# ppc_ddr2_0.net
KiCad netlist of a schematic drawn in Altium Designer
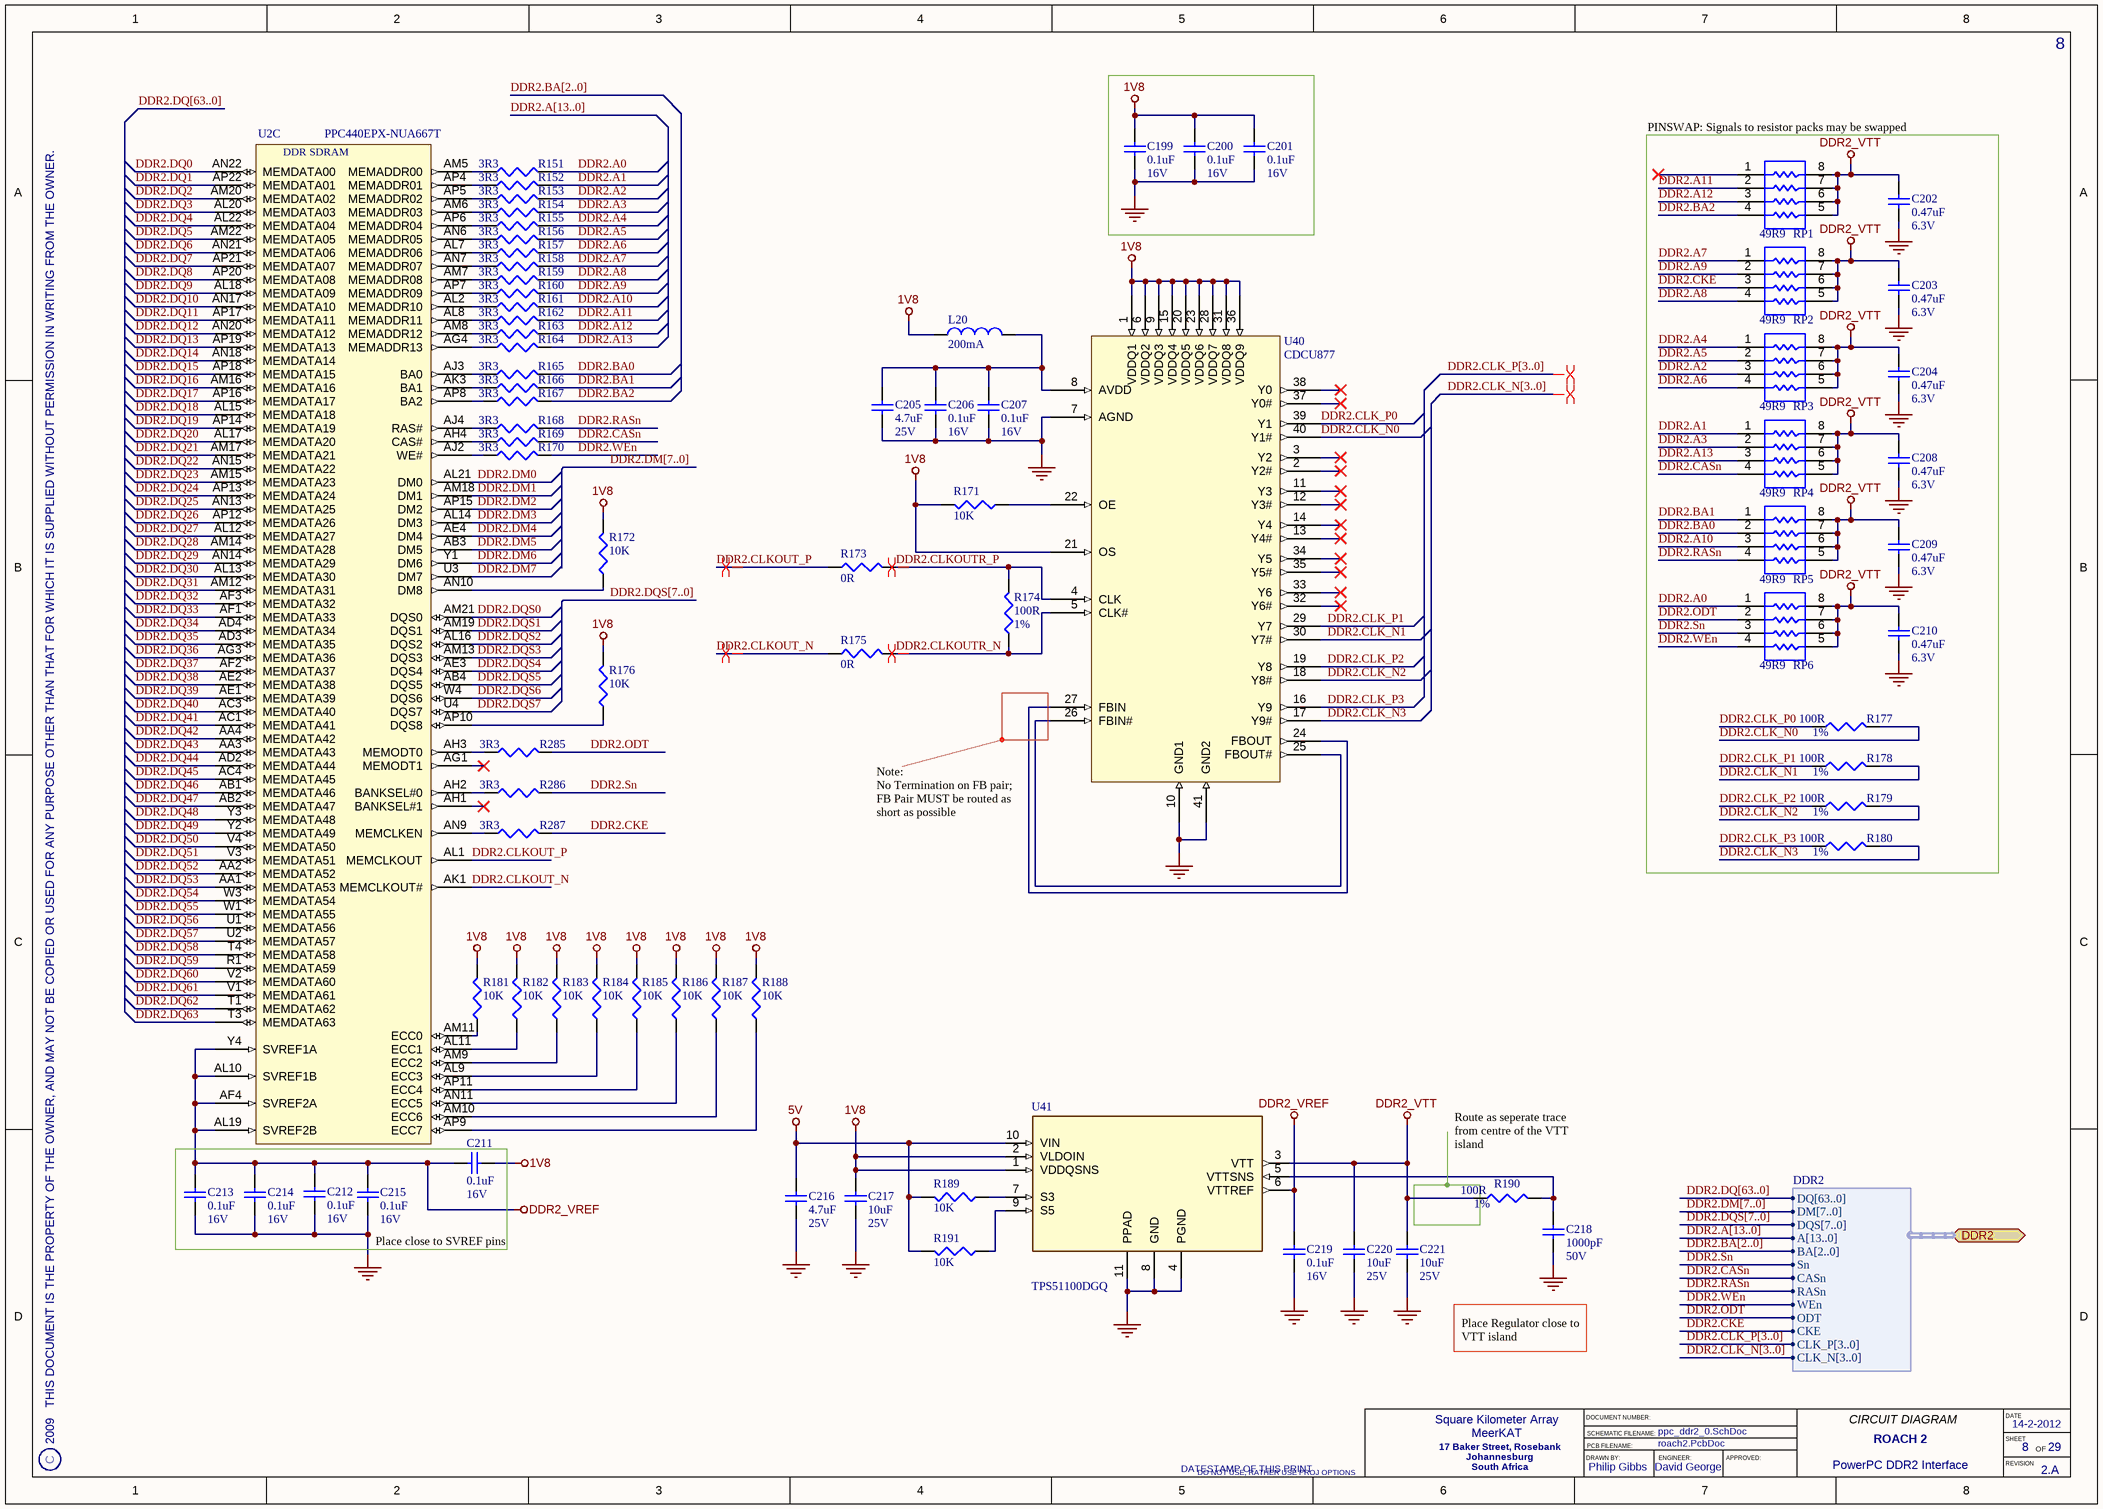
[diagram p0: ppc_ddr2_0.SchDoc]

(export (version "E")
  (design (tool "Eeschema 10.0.6"))
  (components
    (comp (ref "C199")
      (value "0.1uF")
      (footprint "CAPC1005X60L")
      (description "0.1uF, Ceramic Capacitor")
      (fields
        (field (name "RATING") "16V")
        (field (name "MANUFACTURER") "VENKEL")
        (field (name "PARTNUM") "C0402X7R160-104KN")
      )
      (libsource (lib "altium_db") (part "CapStd"))
    )
    (comp (ref "C200")
      (value "0.1uF")
      (footprint "CAPC1005X60L")
      (description "0.1uF, Ceramic Capacitor")
      (fields
        (field (name "RATING") "16V")
        (field (name "MANUFACTURER") "VENKEL")
        (field (name "PARTNUM") "C0402X7R160-104KN")
      )
      (libsource (lib "altium_db") (part "CapStd"))
    )
    (comp (ref "C201")
      (value "0.1uF")
      (footprint "CAPC1005X60L")
      (description "0.1uF, Ceramic Capacitor")
      (fields
        (field (name "RATING") "16V")
        (field (name "MANUFACTURER") "VENKEL")
        (field (name "PARTNUM") "C0402X7R160-104KN")
      )
      (libsource (lib "altium_db") (part "CapStd"))
    )
    (comp (ref "C202")
      (value "0.47uF")
      (footprint "CAPC1005X55L")
      (description "0.47uF, Ceramic Capacitor")
      (fields
        (field (name "RATING") "6.3V")
        (field (name "MANUFACTURER") "MURATA")
        (field (name "PARTNUM") "GRM155R60J474KE19")
      )
      (libsource (lib "altium_db") (part "CapStd"))
    )
    (comp (ref "C203")
      (value "0.47uF")
      (footprint "CAPC1005X55L")
      (description "0.47uF, Ceramic Capacitor")
      (fields
        (field (name "RATING") "6.3V")
        (field (name "MANUFACTURER") "MURATA")
        (field (name "PARTNUM") "GRM155R60J474KE19")
      )
      (libsource (lib "altium_db") (part "CapStd"))
    )
    (comp (ref "C204")
      (value "0.47uF")
      (footprint "CAPC1005X55L")
      (description "0.47uF, Ceramic Capacitor")
      (fields
        (field (name "RATING") "6.3V")
        (field (name "MANUFACTURER") "MURATA")
        (field (name "PARTNUM") "GRM155R60J474KE19")
      )
      (libsource (lib "altium_db") (part "CapStd"))
    )
    (comp (ref "C205")
      (value "4.7uF")
      (footprint "CAPC2012X127L")
      (description "4.7uF, Ceramic Capacitor")
      (fields
        (field (name "RATING") "25V")
        (field (name "MANUFACTURER") "MURATA")
        (field (name "PARTNUM") "GRM21BR61E475KA12K")
      )
      (libsource (lib "altium_db") (part "CapStd"))
    )
    (comp (ref "C206")
      (value "0.1uF")
      (footprint "CAPC1005X60L")
      (description "0.1uF, Ceramic Capacitor")
      (fields
        (field (name "RATING") "16V")
        (field (name "MANUFACTURER") "VENKEL")
        (field (name "PARTNUM") "C0402X7R160-104KN")
      )
      (libsource (lib "altium_db") (part "CapStd"))
    )
    (comp (ref "C207")
      (value "0.1uF")
      (footprint "CAPC1005X60L")
      (description "0.1uF, Ceramic Capacitor")
      (fields
        (field (name "RATING") "16V")
        (field (name "MANUFACTURER") "VENKEL")
        (field (name "PARTNUM") "C0402X7R160-104KN")
      )
      (libsource (lib "altium_db") (part "CapStd"))
    )
    (comp (ref "C208")
      (value "0.47uF")
      (footprint "CAPC1005X55L")
      (description "0.47uF, Ceramic Capacitor")
      (fields
        (field (name "RATING") "6.3V")
        (field (name "MANUFACTURER") "MURATA")
        (field (name "PARTNUM") "GRM155R60J474KE19")
      )
      (libsource (lib "altium_db") (part "CapStd"))
    )
    (comp (ref "C209")
      (value "0.47uF")
      (footprint "CAPC1005X55L")
      (description "0.47uF, Ceramic Capacitor")
      (fields
        (field (name "RATING") "6.3V")
        (field (name "MANUFACTURER") "MURATA")
        (field (name "PARTNUM") "GRM155R60J474KE19")
      )
      (libsource (lib "altium_db") (part "CapStd"))
    )
    (comp (ref "C210")
      (value "0.47uF")
      (footprint "CAPC1005X55L")
      (description "0.47uF, Ceramic Capacitor")
      (fields
        (field (name "RATING") "6.3V")
        (field (name "MANUFACTURER") "MURATA")
        (field (name "PARTNUM") "GRM155R60J474KE19")
      )
      (libsource (lib "altium_db") (part "CapStd"))
    )
    (comp (ref "C211")
      (value "0.1uF")
      (footprint "CAPC1005X60L")
      (description "0.1uF, Ceramic Capacitor")
      (fields
        (field (name "RATING") "16V")
        (field (name "MANUFACTURER") "VENKEL")
        (field (name "PARTNUM") "C0402X7R160-104KN")
      )
      (libsource (lib "altium_db") (part "CapStd"))
    )
    (comp (ref "C212")
      (value "0.1uF")
      (footprint "CAPC1005X60L")
      (description "0.1uF, Ceramic Capacitor")
      (fields
        (field (name "RATING") "16V")
        (field (name "MANUFACTURER") "VENKEL")
        (field (name "PARTNUM") "C0402X7R160-104KN")
      )
      (libsource (lib "altium_db") (part "CapStd"))
    )
    (comp (ref "C213")
      (value "0.1uF")
      (footprint "CAPC1005X60L")
      (description "0.1uF, Ceramic Capacitor")
      (fields
        (field (name "RATING") "16V")
        (field (name "MANUFACTURER") "VENKEL")
        (field (name "PARTNUM") "C0402X7R160-104KN")
      )
      (libsource (lib "altium_db") (part "CapStd"))
    )
    (comp (ref "C214")
      (value "0.1uF")
      (footprint "CAPC1005X60L")
      (description "0.1uF, Ceramic Capacitor")
      (fields
        (field (name "RATING") "16V")
        (field (name "MANUFACTURER") "VENKEL")
        (field (name "PARTNUM") "C0402X7R160-104KN")
      )
      (libsource (lib "altium_db") (part "CapStd"))
    )
    (comp (ref "C215")
      (value "0.1uF")
      (footprint "CAPC1005X60L")
      (description "0.1uF, Ceramic Capacitor")
      (fields
        (field (name "RATING") "16V")
        (field (name "MANUFACTURER") "VENKEL")
        (field (name "PARTNUM") "C0402X7R160-104KN")
      )
      (libsource (lib "altium_db") (part "CapStd"))
    )
    (comp (ref "C216")
      (value "4.7uF")
      (footprint "CAPC2012X127L")
      (description "4.7uF, Ceramic Capacitor")
      (fields
        (field (name "RATING") "25V")
        (field (name "MANUFACTURER") "MURATA")
        (field (name "PARTNUM") "GRM21BR61E475KA12K")
      )
      (libsource (lib "altium_db") (part "CapStd"))
    )
    (comp (ref "C217")
      (value "10uF")
      (footprint "CAPC3225X200L")
      (description "10uF, Ceramic Capacitor")
      (fields
        (field (name "RATING") "25V")
        (field (name "MANUFACTURER") "MURATA")
        (field (name "PARTNUM") "GRM32DR61E106KA12L")
      )
      (libsource (lib "altium_db") (part "CapStd"))
    )
    (comp (ref "C218")
      (value "1000pF")
      (footprint "CAPC1005X55L")
      (description "1000pF, Ceramic Capacitor")
      (fields
        (field (name "RATING") "50V")
        (field (name "MANUFACTURER") "MURATA")
        (field (name "PARTNUM") "GRM155R61H102KA01D")
      )
      (libsource (lib "altium_db") (part "CapStd"))
    )
    (comp (ref "C219")
      (value "0.1uF")
      (footprint "CAPC1005X60L")
      (description "0.1uF, Ceramic Capacitor")
      (fields
        (field (name "RATING") "16V")
        (field (name "MANUFACTURER") "VENKEL")
        (field (name "PARTNUM") "C0402X7R160-104KN")
      )
      (libsource (lib "altium_db") (part "CapStd"))
    )
    (comp (ref "C220")
      (value "10uF")
      (footprint "CAPC3225X200L")
      (description "10uF, Ceramic Capacitor")
      (fields
        (field (name "RATING") "25V")
        (field (name "MANUFACTURER") "MURATA")
        (field (name "PARTNUM") "GRM32DR61E106KA12L")
      )
      (libsource (lib "altium_db") (part "CapStd"))
    )
    (comp (ref "C221")
      (value "10uF")
      (footprint "CAPC3225X200L")
      (description "10uF, Ceramic Capacitor")
      (fields
        (field (name "RATING") "25V")
        (field (name "MANUFACTURER") "MURATA")
        (field (name "PARTNUM") "GRM32DR61E106KA12L")
      )
      (libsource (lib "altium_db") (part "CapStd"))
    )
    (comp (ref "L20")
      (value "600R")
      (footprint "INDC2012X130L")
      (description "600 Ohm, Chip Ferrite Bead")
      (fields
        (field (name "RATING") "200mA")
        (field (name "MANUFACTURER") "Murata")
        (field (name "PARTNUM") "BLM21BD601SN1")
      )
      (libsource (lib "altium_db") (part "IndStd"))
    )
    (comp (ref "R151")
      (value "3R3")
      (footprint "RESC1005X40L")
      (description "3R3, 1.1mm x 0.5mm, Thick Film Resistor")
      (fields (field (name "MANUFACTURER") "ROYALOHM") (field (name "PARTNUM") "0402WGJ330KT1E"))
      (libsource (lib "altium_db") (part "ResStd"))
    )
    (comp (ref "R152")
      (value "3R3")
      (footprint "RESC1005X40L")
      (description "3R3, 1.1mm x 0.5mm, Thick Film Resistor")
      (fields (field (name "MANUFACTURER") "ROYALOHM") (field (name "PARTNUM") "0402WGJ330KT1E"))
      (libsource (lib "altium_db") (part "ResStd"))
    )
    (comp (ref "R153")
      (value "3R3")
      (footprint "RESC1005X40L")
      (description "3R3, 1.1mm x 0.5mm, Thick Film Resistor")
      (fields (field (name "MANUFACTURER") "ROYALOHM") (field (name "PARTNUM") "0402WGJ330KT1E"))
      (libsource (lib "altium_db") (part "ResStd"))
    )
    (comp (ref "R154")
      (value "3R3")
      (footprint "RESC1005X40L")
      (description "3R3, 1.1mm x 0.5mm, Thick Film Resistor")
      (fields (field (name "MANUFACTURER") "ROYALOHM") (field (name "PARTNUM") "0402WGJ330KT1E"))
      (libsource (lib "altium_db") (part "ResStd"))
    )
    (comp (ref "R155")
      (value "3R3")
      (footprint "RESC1005X40L")
      (description "3R3, 1.1mm x 0.5mm, Thick Film Resistor")
      (fields (field (name "MANUFACTURER") "ROYALOHM") (field (name "PARTNUM") "0402WGJ330KT1E"))
      (libsource (lib "altium_db") (part "ResStd"))
    )
    (comp (ref "R156")
      (value "3R3")
      (footprint "RESC1005X40L")
      (description "3R3, 1.1mm x 0.5mm, Thick Film Resistor")
      (fields (field (name "MANUFACTURER") "ROYALOHM") (field (name "PARTNUM") "0402WGJ330KT1E"))
      (libsource (lib "altium_db") (part "ResStd"))
    )
    (comp (ref "R157")
      (value "3R3")
      (footprint "RESC1005X40L")
      (description "3R3, 1.1mm x 0.5mm, Thick Film Resistor")
      (fields (field (name "MANUFACTURER") "ROYALOHM") (field (name "PARTNUM") "0402WGJ330KT1E"))
      (libsource (lib "altium_db") (part "ResStd"))
    )
    (comp (ref "R158")
      (value "3R3")
      (footprint "RESC1005X40L")
      (description "3R3, 1.1mm x 0.5mm, Thick Film Resistor")
      (fields (field (name "MANUFACTURER") "ROYALOHM") (field (name "PARTNUM") "0402WGJ330KT1E"))
      (libsource (lib "altium_db") (part "ResStd"))
    )
    (comp (ref "R159")
      (value "3R3")
      (footprint "RESC1005X40L")
      (description "3R3, 1.1mm x 0.5mm, Thick Film Resistor")
      (fields (field (name "MANUFACTURER") "ROYALOHM") (field (name "PARTNUM") "0402WGJ330KT1E"))
      (libsource (lib "altium_db") (part "ResStd"))
    )
    (comp (ref "R160")
      (value "3R3")
      (footprint "RESC1005X40L")
      (description "3R3, 1.1mm x 0.5mm, Thick Film Resistor")
      (fields (field (name "MANUFACTURER") "ROYALOHM") (field (name "PARTNUM") "0402WGJ330KT1E"))
      (libsource (lib "altium_db") (part "ResStd"))
    )
    (comp (ref "R161")
      (value "3R3")
      (footprint "RESC1005X40L")
      (description "3R3, 1.1mm x 0.5mm, Thick Film Resistor")
      (fields (field (name "MANUFACTURER") "ROYALOHM") (field (name "PARTNUM") "0402WGJ330KT1E"))
      (libsource (lib "altium_db") (part "ResStd"))
    )
    (comp (ref "R162")
      (value "3R3")
      (footprint "RESC1005X40L")
      (description "3R3, 1.1mm x 0.5mm, Thick Film Resistor")
      (fields (field (name "MANUFACTURER") "ROYALOHM") (field (name "PARTNUM") "0402WGJ330KT1E"))
      (libsource (lib "altium_db") (part "ResStd"))
    )
    (comp (ref "R163")
      (value "3R3")
      (footprint "RESC1005X40L")
      (description "3R3, 1.1mm x 0.5mm, Thick Film Resistor")
      (fields (field (name "MANUFACTURER") "ROYALOHM") (field (name "PARTNUM") "0402WGJ330KT1E"))
      (libsource (lib "altium_db") (part "ResStd"))
    )
    (comp (ref "R164")
      (value "3R3")
      (footprint "RESC1005X40L")
      (description "3R3, 1.1mm x 0.5mm, Thick Film Resistor")
      (fields (field (name "MANUFACTURER") "ROYALOHM") (field (name "PARTNUM") "0402WGJ330KT1E"))
      (libsource (lib "altium_db") (part "ResStd"))
    )
    (comp (ref "R165")
      (value "3R3")
      (footprint "RESC1005X40L")
      (description "3R3, 1.1mm x 0.5mm, Thick Film Resistor")
      (fields (field (name "MANUFACTURER") "ROYALOHM") (field (name "PARTNUM") "0402WGJ330KT1E"))
      (libsource (lib "altium_db") (part "ResStd"))
    )
    (comp (ref "R166")
      (value "3R3")
      (footprint "RESC1005X40L")
      (description "3R3, 1.1mm x 0.5mm, Thick Film Resistor")
      (fields (field (name "MANUFACTURER") "ROYALOHM") (field (name "PARTNUM") "0402WGJ330KT1E"))
      (libsource (lib "altium_db") (part "ResStd"))
    )
    (comp (ref "R167")
      (value "3R3")
      (footprint "RESC1005X40L")
      (description "3R3, 1.1mm x 0.5mm, Thick Film Resistor")
      (fields (field (name "MANUFACTURER") "ROYALOHM") (field (name "PARTNUM") "0402WGJ330KT1E"))
      (libsource (lib "altium_db") (part "ResStd"))
    )
    (comp (ref "R168")
      (value "3R3")
      (footprint "RESC1005X40L")
      (description "3R3, 1.1mm x 0.5mm, Thick Film Resistor")
      (fields (field (name "MANUFACTURER") "ROYALOHM") (field (name "PARTNUM") "0402WGJ330KT1E"))
      (libsource (lib "altium_db") (part "ResStd"))
    )
    (comp (ref "R169")
      (value "3R3")
      (footprint "RESC1005X40L")
      (description "3R3, 1.1mm x 0.5mm, Thick Film Resistor")
      (fields (field (name "MANUFACTURER") "ROYALOHM") (field (name "PARTNUM") "0402WGJ330KT1E"))
      (libsource (lib "altium_db") (part "ResStd"))
    )
    (comp (ref "R170")
      (value "3R3")
      (footprint "RESC1005X40L")
      (description "3R3, 1.1mm x 0.5mm, Thick Film Resistor")
      (fields (field (name "MANUFACTURER") "ROYALOHM") (field (name "PARTNUM") "0402WGJ330KT1E"))
      (libsource (lib "altium_db") (part "ResStd"))
    )
    (comp (ref "R171")
      (value "10K")
      (footprint "RESC1005X40L")
      (description "10K, 1.1mm x 0.5mm, Thick Film Resistor")
      (fields (field (name "MANUFACTURER") "ROYALOHM") (field (name "PARTNUM") "0402WGJ0103T1E"))
      (libsource (lib "altium_db") (part "ResStd"))
    )
    (comp (ref "R172")
      (value "10K")
      (footprint "RESC1005X40L")
      (description "10K, 1.1mm x 0.5mm, Thick Film Resistor")
      (fields (field (name "MANUFACTURER") "ROYALOHM") (field (name "PARTNUM") "0402WGJ0103T1E"))
      (libsource (lib "altium_db") (part "ResStd"))
    )
    (comp (ref "R173")
      (value "0R")
      (footprint "RESC1005X40L")
      (description "0R, 1.1mm x 0.5mm, Thick Film Resistor")
      (fields (field (name "MANUFACTURER") "ROYALOHM") (field (name "PARTNUM") "0402WG00000T1E"))
      (libsource (lib "altium_db") (part "ResStd"))
    )
    (comp (ref "R174")
      (value "100R")
      (footprint "RESC1005X40L")
      (description "100R, 1.1mm x 0.5mm, Thick Film Resistor")
      (fields
        (field (name "MANUFACTURER") "ROYALOHM")
        (field (name "PARTNUM") "0402WGF0101T1E")
        (field (name "TOLERANCE") "1%")
      )
      (libsource (lib "altium_db") (part "ResStd"))
    )
    (comp (ref "R175")
      (value "0R")
      (footprint "RESC1005X40L")
      (description "0R, 1.1mm x 0.5mm, Thick Film Resistor")
      (fields (field (name "MANUFACTURER") "ROYALOHM") (field (name "PARTNUM") "0402WG00000T1E"))
      (libsource (lib "altium_db") (part "ResStd"))
    )
    (comp (ref "R176")
      (value "10K")
      (footprint "RESC1005X40L")
      (description "10K, 1.1mm x 0.5mm, Thick Film Resistor")
      (fields (field (name "MANUFACTURER") "ROYALOHM") (field (name "PARTNUM") "0402WGJ0103T1E"))
      (libsource (lib "altium_db") (part "ResStd"))
    )
    (comp (ref "R177")
      (value "100R")
      (footprint "RESC1005X40L")
      (description "100R, 1.1mm x 0.5mm, Thick Film Resistor")
      (fields
        (field (name "MANUFACTURER") "ROYALOHM")
        (field (name "PARTNUM") "0402WGF0101T1E")
        (field (name "TOLERANCE") "1%")
      )
      (libsource (lib "altium_db") (part "ResStd"))
    )
    (comp (ref "R178")
      (value "100R")
      (footprint "RESC1005X40L")
      (description "100R, 1.1mm x 0.5mm, Thick Film Resistor")
      (fields
        (field (name "MANUFACTURER") "ROYALOHM")
        (field (name "PARTNUM") "0402WGF0101T1E")
        (field (name "TOLERANCE") "1%")
      )
      (libsource (lib "altium_db") (part "ResStd"))
    )
    (comp (ref "R179")
      (value "100R")
      (footprint "RESC1005X40L")
      (description "100R, 1.1mm x 0.5mm, Thick Film Resistor")
      (fields
        (field (name "MANUFACTURER") "ROYALOHM")
        (field (name "PARTNUM") "0402WGF0101T1E")
        (field (name "TOLERANCE") "1%")
      )
      (libsource (lib "altium_db") (part "ResStd"))
    )
    (comp (ref "R180")
      (value "100R")
      (footprint "RESC1005X40L")
      (description "100R, 1.1mm x 0.5mm, Thick Film Resistor")
      (fields
        (field (name "MANUFACTURER") "ROYALOHM")
        (field (name "PARTNUM") "0402WGF0101T1E")
        (field (name "TOLERANCE") "1%")
      )
      (libsource (lib "altium_db") (part "ResStd"))
    )
    (comp (ref "R181")
      (value "10K")
      (footprint "RESC1005X40L")
      (description "10K, 1.1mm x 0.5mm, Thick Film Resistor")
      (fields (field (name "MANUFACTURER") "ROYALOHM") (field (name "PARTNUM") "0402WGJ0103T1E"))
      (libsource (lib "altium_db") (part "ResStd"))
    )
    (comp (ref "R182")
      (value "10K")
      (footprint "RESC1005X40L")
      (description "10K, 1.1mm x 0.5mm, Thick Film Resistor")
      (fields (field (name "MANUFACTURER") "ROYALOHM") (field (name "PARTNUM") "0402WGJ0103T1E"))
      (libsource (lib "altium_db") (part "ResStd"))
    )
    (comp (ref "R183")
      (value "10K")
      (footprint "RESC1005X40L")
      (description "10K, 1.1mm x 0.5mm, Thick Film Resistor")
      (fields (field (name "MANUFACTURER") "ROYALOHM") (field (name "PARTNUM") "0402WGJ0103T1E"))
      (libsource (lib "altium_db") (part "ResStd"))
    )
    (comp (ref "R184")
      (value "10K")
      (footprint "RESC1005X40L")
      (description "10K, 1.1mm x 0.5mm, Thick Film Resistor")
      (fields (field (name "MANUFACTURER") "ROYALOHM") (field (name "PARTNUM") "0402WGJ0103T1E"))
      (libsource (lib "altium_db") (part "ResStd"))
    )
    (comp (ref "R185")
      (value "10K")
      (footprint "RESC1005X40L")
      (description "10K, 1.1mm x 0.5mm, Thick Film Resistor")
      (fields (field (name "MANUFACTURER") "ROYALOHM") (field (name "PARTNUM") "0402WGJ0103T1E"))
      (libsource (lib "altium_db") (part "ResStd"))
    )
    (comp (ref "R186")
      (value "10K")
      (footprint "RESC1005X40L")
      (description "10K, 1.1mm x 0.5mm, Thick Film Resistor")
      (fields (field (name "MANUFACTURER") "ROYALOHM") (field (name "PARTNUM") "0402WGJ0103T1E"))
      (libsource (lib "altium_db") (part "ResStd"))
    )
    (comp (ref "R187")
      (value "10K")
      (footprint "RESC1005X40L")
      (description "10K, 1.1mm x 0.5mm, Thick Film Resistor")
      (fields (field (name "MANUFACTURER") "ROYALOHM") (field (name "PARTNUM") "0402WGJ0103T1E"))
      (libsource (lib "altium_db") (part "ResStd"))
    )
    (comp (ref "R188")
      (value "10K")
      (footprint "RESC1005X40L")
      (description "10K, 1.1mm x 0.5mm, Thick Film Resistor")
      (fields (field (name "MANUFACTURER") "ROYALOHM") (field (name "PARTNUM") "0402WGJ0103T1E"))
      (libsource (lib "altium_db") (part "ResStd"))
    )
    (comp (ref "R189")
      (value "10K")
      (footprint "RESC1005X40L")
      (description "10K, 1.1mm x 0.5mm, Thick Film Resistor")
      (fields (field (name "MANUFACTURER") "ROYALOHM") (field (name "PARTNUM") "0402WGJ0103T1E"))
      (libsource (lib "altium_db") (part "ResStd"))
    )
    (comp (ref "R190")
      (value "100R")
      (footprint "RESC1005X40L")
      (description "100R, 1.1mm x 0.5mm, Thick Film Resistor")
      (fields
        (field (name "MANUFACTURER") "ROYALOHM")
        (field (name "PARTNUM") "0402WGF0101T1E")
        (field (name "TOLERANCE") "1%")
      )
      (libsource (lib "altium_db") (part "ResStd"))
    )
    (comp (ref "R191")
      (value "10K")
      (footprint "RESC1005X40L")
      (description "10K, 1.1mm x 0.5mm, Thick Film Resistor")
      (fields (field (name "MANUFACTURER") "ROYALOHM") (field (name "PARTNUM") "0402WGJ0103T1E"))
      (libsource (lib "altium_db") (part "ResStd"))
    )
    (comp (ref "R285")
      (value "3R3")
      (footprint "RESC1005X40L")
      (description "3R3, 1.1mm x 0.5mm, Thick Film Resistor")
      (fields (field (name "MANUFACTURER") "ROYALOHM") (field (name "PARTNUM") "0402WGJ330KT1E"))
      (libsource (lib "altium_db") (part "ResStd"))
    )
    (comp (ref "R286")
      (value "3R3")
      (footprint "RESC1005X40L")
      (description "3R3, 1.1mm x 0.5mm, Thick Film Resistor")
      (fields (field (name "MANUFACTURER") "ROYALOHM") (field (name "PARTNUM") "0402WGJ330KT1E"))
      (libsource (lib "altium_db") (part "ResStd"))
    )
    (comp (ref "R287")
      (value "3R3")
      (footprint "RESC1005X40L")
      (description "3R3, 1.1mm x 0.5mm, Thick Film Resistor")
      (fields (field (name "MANUFACTURER") "ROYALOHM") (field (name "PARTNUM") "0402WGJ330KT1E"))
      (libsource (lib "altium_db") (part "ResStd"))
    )
    (comp (ref "RP1")
      (value "49R9")
      (footprint "RESCAV50P100X200X45-8L")
      (description "4-Wide, Isolated, Thick Film Resistor Network")
      (fields (field (name "MANUFACTURER") "ROYALOHM") (field (name "PARTNUM") "4D02WGJ0510B1E"))
      (libsource (lib "altium_db") (part "ResPack4"))
    )
    (comp (ref "RP2")
      (value "49R9")
      (footprint "RESCAV50P100X200X45-8L")
      (description "4-Wide, Isolated, Thick Film Resistor Network")
      (fields (field (name "MANUFACTURER") "ROYALOHM") (field (name "PARTNUM") "4D02WGJ0510B1E"))
      (libsource (lib "altium_db") (part "ResPack4"))
    )
    (comp (ref "RP3")
      (value "49R9")
      (footprint "RESCAV50P100X200X45-8L")
      (description "4-Wide, Isolated, Thick Film Resistor Network")
      (fields (field (name "MANUFACTURER") "ROYALOHM") (field (name "PARTNUM") "4D02WGJ0510B1E"))
      (libsource (lib "altium_db") (part "ResPack4"))
    )
    (comp (ref "RP4")
      (value "49R9")
      (footprint "RESCAV50P100X200X45-8L")
      (description "4-Wide, Isolated, Thick Film Resistor Network")
      (fields (field (name "MANUFACTURER") "ROYALOHM") (field (name "PARTNUM") "4D02WGJ0510B1E"))
      (libsource (lib "altium_db") (part "ResPack4"))
    )
    (comp (ref "RP5")
      (value "49R9")
      (footprint "RESCAV50P100X200X45-8L")
      (description "4-Wide, Isolated, Thick Film Resistor Network")
      (fields (field (name "MANUFACTURER") "ROYALOHM") (field (name "PARTNUM") "4D02WGJ0510B1E"))
      (libsource (lib "altium_db") (part "ResPack4"))
    )
    (comp (ref "RP6")
      (value "49R9")
      (footprint "RESCAV50P100X200X45-8L")
      (description "4-Wide, Isolated, Thick Film Resistor Network")
      (fields (field (name "MANUFACTURER") "ROYALOHM") (field (name "PARTNUM") "4D02WGJ0510B1E"))
      (libsource (lib "altium_db") (part "ResPack4"))
    )
    (comp (ref "U2")
      (value "PPC440EPX-NUA667T")
      (footprint "TE-PBGA680")
      (description "667MHz, non-RoHS, PPC440EPx uProcessor")
      (fields (field (name "MANUFACTURER") "Applied Micro"))
      (libsource (lib "altium_db") (part "PPC440EPX"))
    )
    (comp (ref "U40")
      (value "CDCU877")
      (footprint "TQFN-40")
      (description "SSTL Zero-Delay Clock Buffer")
      (fields (field (name "MANUFACTURER") "Texas Instruments"))
      (libsource (lib "altium_db") (part "CDCU877"))
    )
    (comp (ref "U41")
      (value "TPS51100DGQ")
      (footprint "MSOP_10-N")
      (description "3A Sink/Source Regulator")
      (fields (field (name "MANUFACTURER") "Texas Instruments"))
      (libsource (lib "altium_db") (part "TPS51100DGQ"))
    )
  )
  (nets
    (net (code "2") (name "/DDR2.A0") (class "Default")
      (node (ref "R151") (pin "2") (pinfunction "2_2") (pintype "passive"))
      (node (ref "RP6") (pin "1") (pinfunction "1_1") (pintype "passive"))
    )
    (net (code "3") (name "/DDR2.A1") (class "Default")
      (node (ref "R152") (pin "2") (pinfunction "2_2") (pintype "passive"))
      (node (ref "RP4") (pin "1") (pinfunction "1_1") (pintype "passive"))
    )
    (net (code "4") (name "/DDR2.A2") (class "Default")
      (node (ref "R153") (pin "2") (pinfunction "2_2") (pintype "passive"))
      (node (ref "RP3") (pin "3") (pinfunction "3_3") (pintype "passive"))
    )
    (net (code "5") (name "/DDR2.A3") (class "Default")
      (node (ref "R154") (pin "2") (pinfunction "2_2") (pintype "passive"))
      (node (ref "RP4") (pin "2") (pinfunction "2_2") (pintype "passive"))
    )
    (net (code "6") (name "/DDR2.A4") (class "Default")
      (node (ref "R155") (pin "2") (pinfunction "2_2") (pintype "passive"))
      (node (ref "RP3") (pin "1") (pinfunction "1_1") (pintype "passive"))
    )
    (net (code "7") (name "/DDR2.A5") (class "Default")
      (node (ref "R156") (pin "2") (pinfunction "2_2") (pintype "passive"))
      (node (ref "RP3") (pin "2") (pinfunction "2_2") (pintype "passive"))
    )
    (net (code "8") (name "/DDR2.A6") (class "Default")
      (node (ref "R157") (pin "2") (pinfunction "2_2") (pintype "passive"))
      (node (ref "RP3") (pin "4") (pinfunction "4_4") (pintype "passive"))
    )
    (net (code "9") (name "/DDR2.A7") (class "Default")
      (node (ref "R158") (pin "2") (pinfunction "2_2") (pintype "passive"))
      (node (ref "RP2") (pin "1") (pinfunction "1_1") (pintype "passive"))
    )
    (net (code "10") (name "/DDR2.A8") (class "Default")
      (node (ref "R159") (pin "2") (pinfunction "2_2") (pintype "passive"))
      (node (ref "RP2") (pin "4") (pinfunction "4_4") (pintype "passive"))
    )
    (net (code "11") (name "/DDR2.A9") (class "Default")
      (node (ref "R160") (pin "2") (pinfunction "2_2") (pintype "passive"))
      (node (ref "RP2") (pin "2") (pinfunction "2_2") (pintype "passive"))
    )
    (net (code "12") (name "/DDR2.A10") (class "Default")
      (node (ref "R161") (pin "2") (pinfunction "2_2") (pintype "passive"))
      (node (ref "RP5") (pin "3") (pinfunction "3_3") (pintype "passive"))
    )
    (net (code "13") (name "/DDR2.A11") (class "Default")
      (node (ref "R162") (pin "2") (pinfunction "2_2") (pintype "passive"))
      (node (ref "RP1") (pin "2") (pinfunction "2_2") (pintype "passive"))
    )
    (net (code "14") (name "/DDR2.A12") (class "Default")
      (node (ref "R163") (pin "2") (pinfunction "2_2") (pintype "passive"))
      (node (ref "RP1") (pin "3") (pinfunction "3_3") (pintype "passive"))
    )
    (net (code "15") (name "/DDR2.A13") (class "Default")
      (node (ref "R164") (pin "2") (pinfunction "2_2") (pintype "passive"))
      (node (ref "RP4") (pin "3") (pinfunction "3_3") (pintype "passive"))
    )
    (net (code "17") (name "/DDR2.BA0") (class "Default")
      (node (ref "R165") (pin "2") (pinfunction "2_2") (pintype "passive"))
      (node (ref "RP5") (pin "2") (pinfunction "2_2") (pintype "passive"))
    )
    (net (code "18") (name "/DDR2.BA1") (class "Default")
      (node (ref "R166") (pin "2") (pinfunction "2_2") (pintype "passive"))
      (node (ref "RP5") (pin "1") (pinfunction "1_1") (pintype "passive"))
    )
    (net (code "19") (name "/DDR2.BA2") (class "Default")
      (node (ref "R167") (pin "2") (pinfunction "2_2") (pintype "passive"))
      (node (ref "RP1") (pin "4") (pinfunction "4_4") (pintype "passive"))
    )
    (net (code "21") (name "/DDR2.CASn") (class "Default")
      (node (ref "R169") (pin "2") (pinfunction "2_2") (pintype "passive"))
      (node (ref "RP4") (pin "4") (pinfunction "4_4") (pintype "passive"))
    )
    (net (code "22") (name "/DDR2.CKE") (class "Default")
      (node (ref "R287") (pin "2") (pinfunction "2_2") (pintype "passive"))
      (node (ref "RP2") (pin "3") (pinfunction "3_3") (pintype "passive"))
    )
    (net (code "23") (name "/DDR2.CLKOUTR_N") (class "Default")
      (node (ref "R174") (pin "1") (pinfunction "1_1") (pintype "passive"))
      (node (ref "R175") (pin "2") (pinfunction "2_2") (pintype "passive"))
      (node (ref "U40") (pin "5") (pinfunction "CLK#_5") (pintype "input"))
    )
    (net (code "24") (name "/DDR2.CLKOUTR_P") (class "Default")
      (node (ref "R173") (pin "2") (pinfunction "2_2") (pintype "passive"))
      (node (ref "R174") (pin "2") (pinfunction "2_2") (pintype "passive"))
      (node (ref "U40") (pin "4") (pinfunction "CLK_4") (pintype "input"))
    )
    (net (code "25") (name "/DDR2.CLKOUT_N") (class "Default")
      (node (ref "R175") (pin "1") (pinfunction "1_1") (pintype "passive"))
      (node (ref "U2") (pin "AK1") (pinfunction "MEMCLKOUT#_AK1") (pintype "output"))
    )
    (net (code "26") (name "/DDR2.CLKOUT_P") (class "Default")
      (node (ref "R173") (pin "1") (pinfunction "1_1") (pintype "passive"))
      (node (ref "U2") (pin "AL1") (pinfunction "MEMCLKOUT_AL1") (pintype "output"))
    )
    (net (code "27") (name "/DDR2.CLK_N0") (class "Default")
      (node (ref "R177") (pin "2") (pinfunction "2_2") (pintype "passive"))
      (node (ref "U40") (pin "40") (pinfunction "Y1#_40") (pintype "output"))
    )
    (net (code "28") (name "/DDR2.CLK_N1") (class "Default")
      (node (ref "R178") (pin "2") (pinfunction "2_2") (pintype "passive"))
      (node (ref "U40") (pin "30") (pinfunction "Y7#_30") (pintype "output"))
    )
    (net (code "29") (name "/DDR2.CLK_N2") (class "Default")
      (node (ref "R179") (pin "2") (pinfunction "2_2") (pintype "passive"))
      (node (ref "U40") (pin "18") (pinfunction "Y8#_18") (pintype "output"))
    )
    (net (code "30") (name "/DDR2.CLK_N3") (class "Default")
      (node (ref "R180") (pin "2") (pinfunction "2_2") (pintype "passive"))
      (node (ref "U40") (pin "17") (pinfunction "Y9#_17") (pintype "output"))
    )
    (net (code "32") (name "/DDR2.CLK_P0") (class "Default")
      (node (ref "R177") (pin "1") (pinfunction "1_1") (pintype "passive"))
      (node (ref "U40") (pin "39") (pinfunction "Y1_39") (pintype "output"))
    )
    (net (code "33") (name "/DDR2.CLK_P1") (class "Default")
      (node (ref "R178") (pin "1") (pinfunction "1_1") (pintype "passive"))
      (node (ref "U40") (pin "29") (pinfunction "Y7_29") (pintype "output"))
    )
    (net (code "34") (name "/DDR2.CLK_P2") (class "Default")
      (node (ref "R179") (pin "1") (pinfunction "1_1") (pintype "passive"))
      (node (ref "U40") (pin "19") (pinfunction "Y8_19") (pintype "output"))
    )
    (net (code "35") (name "/DDR2.CLK_P3") (class "Default")
      (node (ref "R180") (pin "1") (pinfunction "1_1") (pintype "passive"))
      (node (ref "U40") (pin "16") (pinfunction "Y9_16") (pintype "output"))
    )
    (net (code "37") (name "/DDR2.DM0") (class "Default")
      (node (ref "U2") (pin "AL21") (pinfunction "DM0_AL21") (pintype "output"))
    )
    (net (code "38") (name "/DDR2.DM1") (class "Default")
      (node (ref "U2") (pin "AM18") (pinfunction "DM1_AM18") (pintype "output"))
    )
    (net (code "39") (name "/DDR2.DM2") (class "Default")
      (node (ref "U2") (pin "AP15") (pinfunction "DM2_AP15") (pintype "output"))
    )
    (net (code "40") (name "/DDR2.DM3") (class "Default")
      (node (ref "U2") (pin "AL14") (pinfunction "DM3_AL14") (pintype "output"))
    )
    (net (code "41") (name "/DDR2.DM4") (class "Default")
      (node (ref "U2") (pin "AE4") (pinfunction "DM4_AE4") (pintype "output"))
    )
    (net (code "42") (name "/DDR2.DM5") (class "Default")
      (node (ref "U2") (pin "AB3") (pinfunction "DM5_AB3") (pintype "output"))
    )
    (net (code "43") (name "/DDR2.DM6") (class "Default")
      (node (ref "U2") (pin "Y1") (pinfunction "DM6_Y1") (pintype "output"))
    )
    (net (code "44") (name "/DDR2.DM7") (class "Default")
      (node (ref "U2") (pin "U3") (pinfunction "DM7_U3") (pintype "output"))
    )
    (net (code "46") (name "/DDR2.DQ0") (class "Default")
      (node (ref "U2") (pin "AN22") (pinfunction "MEMDATA00_AN22") (pintype "bidirectional"))
    )
    (net (code "47") (name "/DDR2.DQ1") (class "Default")
      (node (ref "U2") (pin "AP22") (pinfunction "MEMDATA01_AP22") (pintype "bidirectional"))
    )
    (net (code "48") (name "/DDR2.DQ2") (class "Default")
      (node (ref "U2") (pin "AM20") (pinfunction "MEMDATA02_AM20") (pintype "bidirectional"))
    )
    (net (code "49") (name "/DDR2.DQ3") (class "Default")
      (node (ref "U2") (pin "AL20") (pinfunction "MEMDATA03_AL20") (pintype "bidirectional"))
    )
    (net (code "50") (name "/DDR2.DQ4") (class "Default")
      (node (ref "U2") (pin "AL22") (pinfunction "MEMDATA04_AL22") (pintype "bidirectional"))
    )
    (net (code "51") (name "/DDR2.DQ5") (class "Default")
      (node (ref "U2") (pin "AM22") (pinfunction "MEMDATA05_AM22") (pintype "bidirectional"))
    )
    (net (code "52") (name "/DDR2.DQ6") (class "Default")
      (node (ref "U2") (pin "AN21") (pinfunction "MEMDATA06_AN21") (pintype "bidirectional"))
    )
    (net (code "53") (name "/DDR2.DQ7") (class "Default")
      (node (ref "U2") (pin "AP21") (pinfunction "MEMDATA07_AP21") (pintype "bidirectional"))
    )
    (net (code "54") (name "/DDR2.DQ8") (class "Default")
      (node (ref "U2") (pin "AP20") (pinfunction "MEMDATA08_AP20") (pintype "bidirectional"))
    )
    (net (code "55") (name "/DDR2.DQ9") (class "Default")
      (node (ref "U2") (pin "AL18") (pinfunction "MEMDATA09_AL18") (pintype "bidirectional"))
    )
    (net (code "56") (name "/DDR2.DQ10") (class "Default")
      (node (ref "U2") (pin "AN17") (pinfunction "MEMDATA10_AN17") (pintype "bidirectional"))
    )
    (net (code "57") (name "/DDR2.DQ11") (class "Default")
      (node (ref "U2") (pin "AP17") (pinfunction "MEMDATA11_AP17") (pintype "bidirectional"))
    )
    (net (code "58") (name "/DDR2.DQ12") (class "Default")
      (node (ref "U2") (pin "AN20") (pinfunction "MEMDATA12_AN20") (pintype "bidirectional"))
    )
    (net (code "59") (name "/DDR2.DQ13") (class "Default")
      (node (ref "U2") (pin "AP19") (pinfunction "MEMDATA13_AP19") (pintype "bidirectional"))
    )
    (net (code "60") (name "/DDR2.DQ14") (class "Default")
      (node (ref "U2") (pin "AN18") (pinfunction "MEMDATA14_AN18") (pintype "bidirectional"))
    )
    (net (code "61") (name "/DDR2.DQ15") (class "Default")
      (node (ref "U2") (pin "AP18") (pinfunction "MEMDATA15_AP18") (pintype "bidirectional"))
    )
    (net (code "62") (name "/DDR2.DQ16") (class "Default")
      (node (ref "U2") (pin "AM16") (pinfunction "MEMDATA16_AM16") (pintype "bidirectional"))
    )
    (net (code "63") (name "/DDR2.DQ17") (class "Default")
      (node (ref "U2") (pin "AP16") (pinfunction "MEMDATA17_AP16") (pintype "bidirectional"))
    )
    (net (code "64") (name "/DDR2.DQ18") (class "Default")
      (node (ref "U2") (pin "AL15") (pinfunction "MEMDATA18_AL15") (pintype "bidirectional"))
    )
    (net (code "65") (name "/DDR2.DQ19") (class "Default")
      (node (ref "U2") (pin "AP14") (pinfunction "MEMDATA19_AP14") (pintype "bidirectional"))
    )
    (net (code "66") (name "/DDR2.DQ20") (class "Default")
      (node (ref "U2") (pin "AL17") (pinfunction "MEMDATA20_AL17") (pintype "bidirectional"))
    )
    (net (code "67") (name "/DDR2.DQ21") (class "Default")
      (node (ref "U2") (pin "AM17") (pinfunction "MEMDATA21_AM17") (pintype "bidirectional"))
    )
    (net (code "68") (name "/DDR2.DQ22") (class "Default")
      (node (ref "U2") (pin "AN15") (pinfunction "MEMDATA22_AN15") (pintype "bidirectional"))
    )
    (net (code "69") (name "/DDR2.DQ23") (class "Default")
      (node (ref "U2") (pin "AM15") (pinfunction "MEMDATA23_AM15") (pintype "bidirectional"))
    )
    (net (code "70") (name "/DDR2.DQ24") (class "Default")
      (node (ref "U2") (pin "AP13") (pinfunction "MEMDATA24_AP13") (pintype "bidirectional"))
    )
    (net (code "71") (name "/DDR2.DQ25") (class "Default")
      (node (ref "U2") (pin "AN13") (pinfunction "MEMDATA25_AN13") (pintype "bidirectional"))
    )
    (net (code "72") (name "/DDR2.DQ26") (class "Default")
      (node (ref "U2") (pin "AP12") (pinfunction "MEMDATA26_AP12") (pintype "bidirectional"))
    )
    (net (code "73") (name "/DDR2.DQ27") (class "Default")
      (node (ref "U2") (pin "AL12") (pinfunction "MEMDATA27_AL12") (pintype "bidirectional"))
    )
    (net (code "74") (name "/DDR2.DQ28") (class "Default")
      (node (ref "U2") (pin "AM14") (pinfunction "MEMDATA28_AM14") (pintype "bidirectional"))
    )
    (net (code "75") (name "/DDR2.DQ29") (class "Default")
      (node (ref "U2") (pin "AN14") (pinfunction "MEMDATA29_AN14") (pintype "bidirectional"))
    )
    (net (code "76") (name "/DDR2.DQ30") (class "Default")
      (node (ref "U2") (pin "AL13") (pinfunction "MEMDATA30_AL13") (pintype "bidirectional"))
    )
    (net (code "77") (name "/DDR2.DQ31") (class "Default")
      (node (ref "U2") (pin "AM12") (pinfunction "MEMDATA31_AM12") (pintype "bidirectional"))
    )
    (net (code "78") (name "/DDR2.DQ32") (class "Default")
      (node (ref "U2") (pin "AF3") (pinfunction "MEMDATA32_AF3") (pintype "bidirectional"))
    )
    (net (code "79") (name "/DDR2.DQ33") (class "Default")
      (node (ref "U2") (pin "AF1") (pinfunction "MEMDATA33_AF1") (pintype "bidirectional"))
    )
    (net (code "80") (name "/DDR2.DQ34") (class "Default")
      (node (ref "U2") (pin "AD4") (pinfunction "MEMDATA34_AD4") (pintype "bidirectional"))
    )
    (net (code "81") (name "/DDR2.DQ35") (class "Default")
      (node (ref "U2") (pin "AD3") (pinfunction "MEMDATA35_AD3") (pintype "bidirectional"))
    )
    (net (code "82") (name "/DDR2.DQ36") (class "Default")
      (node (ref "U2") (pin "AG3") (pinfunction "MEMDATA36_AG3") (pintype "bidirectional"))
    )
    (net (code "83") (name "/DDR2.DQ37") (class "Default")
      (node (ref "U2") (pin "AF2") (pinfunction "MEMDATA37_AF2") (pintype "bidirectional"))
    )
    (net (code "84") (name "/DDR2.DQ38") (class "Default")
      (node (ref "U2") (pin "AE2") (pinfunction "MEMDATA38_AE2") (pintype "bidirectional"))
    )
    (net (code "85") (name "/DDR2.DQ39") (class "Default")
      (node (ref "U2") (pin "AE1") (pinfunction "MEMDATA39_AE1") (pintype "bidirectional"))
    )
    (net (code "86") (name "/DDR2.DQ40") (class "Default")
      (node (ref "U2") (pin "AC3") (pinfunction "MEMDATA40_AC3") (pintype "bidirectional"))
    )
    (net (code "87") (name "/DDR2.DQ41") (class "Default")
      (node (ref "U2") (pin "AC1") (pinfunction "MEMDATA41_AC1") (pintype "bidirectional"))
    )
    (net (code "88") (name "/DDR2.DQ42") (class "Default")
      (node (ref "U2") (pin "AA4") (pinfunction "MEMDATA42_AA4") (pintype "bidirectional"))
    )
    (net (code "89") (name "/DDR2.DQ43") (class "Default")
      (node (ref "U2") (pin "AA3") (pinfunction "MEMDATA43_AA3") (pintype "bidirectional"))
    )
    (net (code "90") (name "/DDR2.DQ44") (class "Default")
      (node (ref "U2") (pin "AD2") (pinfunction "MEMDATA44_AD2") (pintype "bidirectional"))
    )
    (net (code "91") (name "/DDR2.DQ45") (class "Default")
      (node (ref "U2") (pin "AC4") (pinfunction "MEMDATA45_AC4") (pintype "bidirectional"))
    )
    (net (code "92") (name "/DDR2.DQ46") (class "Default")
      (node (ref "U2") (pin "AB1") (pinfunction "MEMDATA46_AB1") (pintype "bidirectional"))
    )
    (net (code "93") (name "/DDR2.DQ47") (class "Default")
      (node (ref "U2") (pin "AB2") (pinfunction "MEMDATA47_AB2") (pintype "bidirectional"))
    )
    (net (code "94") (name "/DDR2.DQ48") (class "Default")
      (node (ref "U2") (pin "Y3") (pinfunction "MEMDATA48_Y3") (pintype "bidirectional"))
    )
    (net (code "95") (name "/DDR2.DQ49") (class "Default")
      (node (ref "U2") (pin "Y2") (pinfunction "MEMDATA49_Y2") (pintype "bidirectional"))
    )
    (net (code "96") (name "/DDR2.DQ50") (class "Default")
      (node (ref "U2") (pin "V4") (pinfunction "MEMDATA50_V4") (pintype "bidirectional"))
    )
    (net (code "97") (name "/DDR2.DQ51") (class "Default")
      (node (ref "U2") (pin "V3") (pinfunction "MEMDATA51_V3") (pintype "bidirectional"))
    )
    (net (code "98") (name "/DDR2.DQ52") (class "Default")
      (node (ref "U2") (pin "AA2") (pinfunction "MEMDATA52_AA2") (pintype "bidirectional"))
    )
    (net (code "99") (name "/DDR2.DQ53") (class "Default")
      (node (ref "U2") (pin "AA1") (pinfunction "MEMDATA53_AA1") (pintype "bidirectional"))
    )
    (net (code "100") (name "/DDR2.DQ54") (class "Default")
      (node (ref "U2") (pin "W3") (pinfunction "MEMDATA54_W3") (pintype "bidirectional"))
    )
    (net (code "101") (name "/DDR2.DQ55") (class "Default")
      (node (ref "U2") (pin "W1") (pinfunction "MEMDATA55_W1") (pintype "bidirectional"))
    )
    (net (code "102") (name "/DDR2.DQ56") (class "Default")
      (node (ref "U2") (pin "U1") (pinfunction "MEMDATA56_U1") (pintype "bidirectional"))
    )
    (net (code "103") (name "/DDR2.DQ57") (class "Default")
      (node (ref "U2") (pin "U2") (pinfunction "MEMDATA57_U2") (pintype "bidirectional"))
    )
    (net (code "104") (name "/DDR2.DQ58") (class "Default")
      (node (ref "U2") (pin "T4") (pinfunction "MEMDATA58_T4") (pintype "bidirectional"))
    )
    (net (code "105") (name "/DDR2.DQ59") (class "Default")
      (node (ref "U2") (pin "R1") (pinfunction "MEMDATA59_R1") (pintype "bidirectional"))
    )
    (net (code "106") (name "/DDR2.DQ60") (class "Default")
      (node (ref "U2") (pin "V2") (pinfunction "MEMDATA60_V2") (pintype "bidirectional"))
    )
    (net (code "107") (name "/DDR2.DQ61") (class "Default")
      (node (ref "U2") (pin "V1") (pinfunction "MEMDATA61_V1") (pintype "bidirectional"))
    )
    (net (code "108") (name "/DDR2.DQ62") (class "Default")
      (node (ref "U2") (pin "T1") (pinfunction "MEMDATA62_T1") (pintype "bidirectional"))
    )
    (net (code "109") (name "/DDR2.DQ63") (class "Default")
      (node (ref "U2") (pin "T3") (pinfunction "MEMDATA63_T3") (pintype "bidirectional"))
    )
    (net (code "110") (name "/DDR2.DQS0") (class "Default")
      (node (ref "U2") (pin "AM21") (pinfunction "DQS0_AM21") (pintype "bidirectional"))
    )
    (net (code "111") (name "/DDR2.DQS1") (class "Default")
      (node (ref "U2") (pin "AM19") (pinfunction "DQS1_AM19") (pintype "bidirectional"))
    )
    (net (code "112") (name "/DDR2.DQS2") (class "Default")
      (node (ref "U2") (pin "AL16") (pinfunction "DQS2_AL16") (pintype "bidirectional"))
    )
    (net (code "113") (name "/DDR2.DQS3") (class "Default")
      (node (ref "U2") (pin "AM13") (pinfunction "DQS3_AM13") (pintype "bidirectional"))
    )
    (net (code "114") (name "/DDR2.DQS4") (class "Default")
      (node (ref "U2") (pin "AE3") (pinfunction "DQS4_AE3") (pintype "bidirectional"))
    )
    (net (code "115") (name "/DDR2.DQS5") (class "Default")
      (node (ref "U2") (pin "AB4") (pinfunction "DQS5_AB4") (pintype "bidirectional"))
    )
    (net (code "116") (name "/DDR2.DQS6") (class "Default")
      (node (ref "U2") (pin "W4") (pinfunction "DQS6_W4") (pintype "bidirectional"))
    )
    (net (code "117") (name "/DDR2.DQS7") (class "Default")
      (node (ref "U2") (pin "U4") (pinfunction "DQS7_U4") (pintype "bidirectional"))
    )
    (net (code "120") (name "/DDR2.ODT") (class "Default")
      (node (ref "R285") (pin "2") (pinfunction "2_2") (pintype "passive"))
      (node (ref "RP6") (pin "2") (pinfunction "2_2") (pintype "passive"))
    )
    (net (code "121") (name "/DDR2.RASn") (class "Default")
      (node (ref "R168") (pin "2") (pinfunction "2_2") (pintype "passive"))
      (node (ref "RP5") (pin "4") (pinfunction "4_4") (pintype "passive"))
    )
    (net (code "122") (name "/DDR2.Sn") (class "Default")
      (node (ref "R286") (pin "2") (pinfunction "2_2") (pintype "passive"))
      (node (ref "RP6") (pin "3") (pinfunction "3_3") (pintype "passive"))
    )
    (net (code "123") (name "/DDR2.WEn") (class "Default")
      (node (ref "R170") (pin "2") (pinfunction "2_2") (pintype "passive"))
      (node (ref "RP6") (pin "4") (pinfunction "4_4") (pintype "passive"))
    )
    (net (code "126") (name "1V8") (class "Default")
      (node (ref "C199") (pin "2") (pinfunction "2_2") (pintype "passive"))
      (node (ref "C200") (pin "2") (pinfunction "2_2") (pintype "passive"))
      (node (ref "C201") (pin "2") (pinfunction "2_2") (pintype "passive"))
      (node (ref "C211") (pin "2") (pinfunction "2_2") (pintype "passive"))
      (node (ref "C217") (pin "2") (pinfunction "2_2") (pintype "passive"))
      (node (ref "L20") (pin "1") (pinfunction "1_1") (pintype "passive"))
      (node (ref "R171") (pin "2") (pinfunction "2_2") (pintype "passive"))
      (node (ref "R172") (pin "2") (pinfunction "2_2") (pintype "passive"))
      (node (ref "R176") (pin "2") (pinfunction "2_2") (pintype "passive"))
      (node (ref "R181") (pin "2") (pinfunction "2_2") (pintype "passive"))
      (node (ref "R182") (pin "2") (pinfunction "2_2") (pintype "passive"))
      (node (ref "R183") (pin "2") (pinfunction "2_2") (pintype "passive"))
      (node (ref "R184") (pin "2") (pinfunction "2_2") (pintype "passive"))
      (node (ref "R185") (pin "2") (pinfunction "2_2") (pintype "passive"))
      (node (ref "R186") (pin "2") (pinfunction "2_2") (pintype "passive"))
      (node (ref "R187") (pin "2") (pinfunction "2_2") (pintype "passive"))
      (node (ref "R188") (pin "2") (pinfunction "2_2") (pintype "passive"))
      (node (ref "U40") (pin "1") (pinfunction "VDDQ1_1") (pintype "input"))
      (node (ref "U40") (pin "15") (pinfunction "VDDQ4_15") (pintype "input"))
      (node (ref "U40") (pin "20") (pinfunction "VDDQ5_20") (pintype "input"))
      (node (ref "U40") (pin "21") (pinfunction "OS_21") (pintype "input"))
      (node (ref "U40") (pin "23") (pinfunction "VDDQ6_23") (pintype "input"))
      (node (ref "U40") (pin "28") (pinfunction "VDDQ7_28") (pintype "input"))
      (node (ref "U40") (pin "31") (pinfunction "VDDQ8_31") (pintype "input"))
      (node (ref "U40") (pin "36") (pinfunction "VDDQ9_36") (pintype "input"))
      (node (ref "U40") (pin "6") (pinfunction "VDDQ2_6") (pintype "input"))
      (node (ref "U40") (pin "9") (pinfunction "VDDQ3_9") (pintype "input"))
      (node (ref "U41") (pin "1") (pinfunction "VDDQSNS_1") (pintype "input"))
      (node (ref "U41") (pin "2") (pinfunction "VLDOIN_2") (pintype "input"))
    )
    (net (code "127") (name "5V") (class "Default")
      (node (ref "C216") (pin "2") (pinfunction "2_2") (pintype "passive"))
      (node (ref "R189") (pin "2") (pinfunction "2_2") (pintype "passive"))
      (node (ref "R191") (pin "2") (pinfunction "2_2") (pintype "passive"))
      (node (ref "U41") (pin "10") (pinfunction "VIN_10") (pintype "input"))
    )
    (net (code "128") (name "DDR2_VREF") (class "Default")
      (node (ref "C211") (pin "1") (pinfunction "1_1") (pintype "passive"))
      (node (ref "C212") (pin "2") (pinfunction "2_2") (pintype "passive"))
      (node (ref "C213") (pin "2") (pinfunction "2_2") (pintype "passive"))
      (node (ref "C214") (pin "2") (pinfunction "2_2") (pintype "passive"))
      (node (ref "C215") (pin "2") (pinfunction "2_2") (pintype "passive"))
      (node (ref "C219") (pin "2") (pinfunction "2_2") (pintype "passive"))
      (node (ref "U2") (pin "AF4") (pinfunction "SVREF2A_AF4") (pintype "input"))
      (node (ref "U2") (pin "AL10") (pinfunction "SVREF1B_AL10") (pintype "input"))
      (node (ref "U2") (pin "AL19") (pinfunction "SVREF2B_AL19") (pintype "input"))
      (node (ref "U2") (pin "Y4") (pinfunction "SVREF1A_Y4") (pintype "input"))
      (node (ref "U41") (pin "6") (pinfunction "VTTREF_6") (pintype "output"))
    )
    (net (code "129") (name "DDR2_VTT") (class "Default")
      (node (ref "C202") (pin "2") (pinfunction "2_2") (pintype "passive"))
      (node (ref "C203") (pin "2") (pinfunction "2_2") (pintype "passive"))
      (node (ref "C204") (pin "2") (pinfunction "2_2") (pintype "passive"))
      (node (ref "C208") (pin "2") (pinfunction "2_2") (pintype "passive"))
      (node (ref "C209") (pin "2") (pinfunction "2_2") (pintype "passive"))
      (node (ref "C210") (pin "2") (pinfunction "2_2") (pintype "passive"))
      (node (ref "C220") (pin "2") (pinfunction "2_2") (pintype "passive"))
      (node (ref "C221") (pin "2") (pinfunction "2_2") (pintype "passive"))
      (node (ref "R190") (pin "1") (pinfunction "1_1") (pintype "passive"))
      (node (ref "RP1") (pin "5") (pinfunction "5_5") (pintype "passive"))
      (node (ref "RP1") (pin "6") (pinfunction "6_6") (pintype "passive"))
      (node (ref "RP1") (pin "7") (pinfunction "7_7") (pintype "passive"))
      (node (ref "RP1") (pin "8") (pinfunction "8_8") (pintype "passive"))
      (node (ref "RP2") (pin "5") (pinfunction "5_5") (pintype "passive"))
      (node (ref "RP2") (pin "6") (pinfunction "6_6") (pintype "passive"))
      (node (ref "RP2") (pin "7") (pinfunction "7_7") (pintype "passive"))
      (node (ref "RP2") (pin "8") (pinfunction "8_8") (pintype "passive"))
      (node (ref "RP3") (pin "5") (pinfunction "5_5") (pintype "passive"))
      (node (ref "RP3") (pin "6") (pinfunction "6_6") (pintype "passive"))
      (node (ref "RP3") (pin "7") (pinfunction "7_7") (pintype "passive"))
      (node (ref "RP3") (pin "8") (pinfunction "8_8") (pintype "passive"))
      (node (ref "RP4") (pin "5") (pinfunction "5_5") (pintype "passive"))
      (node (ref "RP4") (pin "6") (pinfunction "6_6") (pintype "passive"))
      (node (ref "RP4") (pin "7") (pinfunction "7_7") (pintype "passive"))
      (node (ref "RP4") (pin "8") (pinfunction "8_8") (pintype "passive"))
      (node (ref "RP5") (pin "5") (pinfunction "5_5") (pintype "passive"))
      (node (ref "RP5") (pin "6") (pinfunction "6_6") (pintype "passive"))
      (node (ref "RP5") (pin "7") (pinfunction "7_7") (pintype "passive"))
      (node (ref "RP5") (pin "8") (pinfunction "8_8") (pintype "passive"))
      (node (ref "RP6") (pin "5") (pinfunction "5_5") (pintype "passive"))
      (node (ref "RP6") (pin "6") (pinfunction "6_6") (pintype "passive"))
      (node (ref "RP6") (pin "7") (pinfunction "7_7") (pintype "passive"))
      (node (ref "RP6") (pin "8") (pinfunction "8_8") (pintype "passive"))
      (node (ref "U41") (pin "3") (pinfunction "VTT_3") (pintype "output"))
    )
    (net (code "130") (name "GND") (class "Default")
      (node (ref "C199") (pin "1") (pinfunction "1_1") (pintype "passive"))
      (node (ref "C200") (pin "1") (pinfunction "1_1") (pintype "passive"))
      (node (ref "C201") (pin "1") (pinfunction "1_1") (pintype "passive"))
      (node (ref "C202") (pin "1") (pinfunction "1_1") (pintype "passive"))
      (node (ref "C203") (pin "1") (pinfunction "1_1") (pintype "passive"))
      (node (ref "C204") (pin "1") (pinfunction "1_1") (pintype "passive"))
      (node (ref "C205") (pin "1") (pinfunction "1_1") (pintype "passive"))
      (node (ref "C206") (pin "1") (pinfunction "1_1") (pintype "passive"))
      (node (ref "C207") (pin "1") (pinfunction "1_1") (pintype "passive"))
      (node (ref "C208") (pin "1") (pinfunction "1_1") (pintype "passive"))
      (node (ref "C209") (pin "1") (pinfunction "1_1") (pintype "passive"))
      (node (ref "C210") (pin "1") (pinfunction "1_1") (pintype "passive"))
      (node (ref "C212") (pin "1") (pinfunction "1_1") (pintype "passive"))
      (node (ref "C213") (pin "1") (pinfunction "1_1") (pintype "passive"))
      (node (ref "C214") (pin "1") (pinfunction "1_1") (pintype "passive"))
      (node (ref "C215") (pin "1") (pinfunction "1_1") (pintype "passive"))
      (node (ref "C216") (pin "1") (pinfunction "1_1") (pintype "passive"))
      (node (ref "C217") (pin "1") (pinfunction "1_1") (pintype "passive"))
      (node (ref "C218") (pin "1") (pinfunction "1_1") (pintype "passive"))
      (node (ref "C219") (pin "1") (pinfunction "1_1") (pintype "passive"))
      (node (ref "C220") (pin "1") (pinfunction "1_1") (pintype "passive"))
      (node (ref "C221") (pin "1") (pinfunction "1_1") (pintype "passive"))
      (node (ref "U40") (pin "10") (pinfunction "GND1_10") (pintype "input"))
      (node (ref "U40") (pin "41") (pinfunction "GND2_41") (pintype "input"))
      (node (ref "U40") (pin "7") (pinfunction "AGND_7") (pintype "input"))
      (node (ref "U41") (pin "11") (pinfunction "PPAD_11") (pintype "passive"))
      (node (ref "U41") (pin "4") (pinfunction "PGND_4") (pintype "passive"))
      (node (ref "U41") (pin "8") (pinfunction "GND_8") (pintype "passive"))
    )
    (net (code "131") (name "Net-(U2C-BA0)") (class "Default")
      (node (ref "R165") (pin "1") (pinfunction "1_1") (pintype "passive"))
      (node (ref "U2") (pin "AJ3") (pinfunction "BA0_AJ3") (pintype "output"))
    )
    (net (code "132") (name "Net-(U2C-BA1)") (class "Default")
      (node (ref "R166") (pin "1") (pinfunction "1_1") (pintype "passive"))
      (node (ref "U2") (pin "AK3") (pinfunction "BA1_AK3") (pintype "output"))
    )
    (net (code "133") (name "Net-(U2C-BA2)") (class "Default")
      (node (ref "R167") (pin "1") (pinfunction "1_1") (pintype "passive"))
      (node (ref "U2") (pin "AP8") (pinfunction "BA2_AP8") (pintype "output"))
    )
    (net (code "134") (name "Net-(U2C-BANKSEL#0)") (class "Default")
      (node (ref "R286") (pin "1") (pinfunction "1_1") (pintype "passive"))
      (node (ref "U2") (pin "AH2") (pinfunction "BANKSEL#0_AH2") (pintype "output"))
    )
    (net (code "135") (name "Net-(U2C-CAS#)") (class "Default")
      (node (ref "R169") (pin "1") (pinfunction "1_1") (pintype "passive"))
      (node (ref "U2") (pin "AH4") (pinfunction "CAS#_AH4") (pintype "output"))
    )
    (net (code "136") (name "Net-(U2C-DM8)") (class "Default")
      (node (ref "R172") (pin "1") (pinfunction "1_1") (pintype "passive"))
      (node (ref "U2") (pin "AN10") (pinfunction "DM8_AN10") (pintype "output"))
    )
    (net (code "137") (name "Net-(U2C-DQS8)") (class "Default")
      (node (ref "R176") (pin "1") (pinfunction "1_1") (pintype "passive"))
      (node (ref "U2") (pin "AP10") (pinfunction "DQS8_AP10") (pintype "bidirectional"))
    )
    (net (code "138") (name "Net-(U2C-ECC0)") (class "Default")
      (node (ref "R181") (pin "1") (pinfunction "1_1") (pintype "passive"))
      (node (ref "U2") (pin "AM11") (pinfunction "ECC0_AM11") (pintype "bidirectional"))
    )
    (net (code "139") (name "Net-(U2C-ECC1)") (class "Default")
      (node (ref "R182") (pin "1") (pinfunction "1_1") (pintype "passive"))
      (node (ref "U2") (pin "AL11") (pinfunction "ECC1_AL11") (pintype "bidirectional"))
    )
    (net (code "140") (name "Net-(U2C-ECC2)") (class "Default")
      (node (ref "R183") (pin "1") (pinfunction "1_1") (pintype "passive"))
      (node (ref "U2") (pin "AM9") (pinfunction "ECC2_AM9") (pintype "bidirectional"))
    )
    (net (code "141") (name "Net-(U2C-ECC3)") (class "Default")
      (node (ref "R184") (pin "1") (pinfunction "1_1") (pintype "passive"))
      (node (ref "U2") (pin "AL9") (pinfunction "ECC3_AL9") (pintype "bidirectional"))
    )
    (net (code "142") (name "Net-(U2C-ECC4)") (class "Default")
      (node (ref "R185") (pin "1") (pinfunction "1_1") (pintype "passive"))
      (node (ref "U2") (pin "AP11") (pinfunction "ECC4_AP11") (pintype "bidirectional"))
    )
    (net (code "143") (name "Net-(U2C-ECC5)") (class "Default")
      (node (ref "R186") (pin "1") (pinfunction "1_1") (pintype "passive"))
      (node (ref "U2") (pin "AN11") (pinfunction "ECC5_AN11") (pintype "bidirectional"))
    )
    (net (code "144") (name "Net-(U2C-ECC6)") (class "Default")
      (node (ref "R187") (pin "1") (pinfunction "1_1") (pintype "passive"))
      (node (ref "U2") (pin "AM10") (pinfunction "ECC6_AM10") (pintype "bidirectional"))
    )
    (net (code "145") (name "Net-(U2C-ECC7)") (class "Default")
      (node (ref "R188") (pin "1") (pinfunction "1_1") (pintype "passive"))
      (node (ref "U2") (pin "AP9") (pinfunction "ECC7_AP9") (pintype "bidirectional"))
    )
    (net (code "146") (name "Net-(U2C-MEMADDR00)") (class "Default")
      (node (ref "R151") (pin "1") (pinfunction "1_1") (pintype "passive"))
      (node (ref "U2") (pin "AM5") (pinfunction "MEMADDR00_AM5") (pintype "output"))
    )
    (net (code "147") (name "Net-(U2C-MEMADDR01)") (class "Default")
      (node (ref "R152") (pin "1") (pinfunction "1_1") (pintype "passive"))
      (node (ref "U2") (pin "AP4") (pinfunction "MEMADDR01_AP4") (pintype "output"))
    )
    (net (code "148") (name "Net-(U2C-MEMADDR02)") (class "Default")
      (node (ref "R153") (pin "1") (pinfunction "1_1") (pintype "passive"))
      (node (ref "U2") (pin "AP5") (pinfunction "MEMADDR02_AP5") (pintype "output"))
    )
    (net (code "149") (name "Net-(U2C-MEMADDR03)") (class "Default")
      (node (ref "R154") (pin "1") (pinfunction "1_1") (pintype "passive"))
      (node (ref "U2") (pin "AM6") (pinfunction "MEMADDR03_AM6") (pintype "output"))
    )
    (net (code "150") (name "Net-(U2C-MEMADDR04)") (class "Default")
      (node (ref "R155") (pin "1") (pinfunction "1_1") (pintype "passive"))
      (node (ref "U2") (pin "AP6") (pinfunction "MEMADDR04_AP6") (pintype "output"))
    )
    (net (code "151") (name "Net-(U2C-MEMADDR05)") (class "Default")
      (node (ref "R156") (pin "1") (pinfunction "1_1") (pintype "passive"))
      (node (ref "U2") (pin "AN6") (pinfunction "MEMADDR05_AN6") (pintype "output"))
    )
    (net (code "152") (name "Net-(U2C-MEMADDR06)") (class "Default")
      (node (ref "R157") (pin "1") (pinfunction "1_1") (pintype "passive"))
      (node (ref "U2") (pin "AL7") (pinfunction "MEMADDR06_AL7") (pintype "output"))
    )
    (net (code "153") (name "Net-(U2C-MEMADDR07)") (class "Default")
      (node (ref "R158") (pin "1") (pinfunction "1_1") (pintype "passive"))
      (node (ref "U2") (pin "AN7") (pinfunction "MEMADDR07_AN7") (pintype "output"))
    )
    (net (code "154") (name "Net-(U2C-MEMADDR08)") (class "Default")
      (node (ref "R159") (pin "1") (pinfunction "1_1") (pintype "passive"))
      (node (ref "U2") (pin "AM7") (pinfunction "MEMADDR08_AM7") (pintype "output"))
    )
    (net (code "155") (name "Net-(U2C-MEMADDR09)") (class "Default")
      (node (ref "R160") (pin "1") (pinfunction "1_1") (pintype "passive"))
      (node (ref "U2") (pin "AP7") (pinfunction "MEMADDR09_AP7") (pintype "output"))
    )
    (net (code "156") (name "Net-(U2C-MEMADDR10)") (class "Default")
      (node (ref "R161") (pin "1") (pinfunction "1_1") (pintype "passive"))
      (node (ref "U2") (pin "AL2") (pinfunction "MEMADDR10_AL2") (pintype "output"))
    )
    (net (code "157") (name "Net-(U2C-MEMADDR11)") (class "Default")
      (node (ref "R162") (pin "1") (pinfunction "1_1") (pintype "passive"))
      (node (ref "U2") (pin "AL8") (pinfunction "MEMADDR11_AL8") (pintype "output"))
    )
    (net (code "158") (name "Net-(U2C-MEMADDR12)") (class "Default")
      (node (ref "R163") (pin "1") (pinfunction "1_1") (pintype "passive"))
      (node (ref "U2") (pin "AM8") (pinfunction "MEMADDR12_AM8") (pintype "output"))
    )
    (net (code "159") (name "Net-(U2C-MEMADDR13)") (class "Default")
      (node (ref "R164") (pin "1") (pinfunction "1_1") (pintype "passive"))
      (node (ref "U2") (pin "AG4") (pinfunction "MEMADDR13_AG4") (pintype "output"))
    )
    (net (code "160") (name "Net-(U2C-MEMCLKEN)") (class "Default")
      (node (ref "R287") (pin "1") (pinfunction "1_1") (pintype "passive"))
      (node (ref "U2") (pin "AN9") (pinfunction "MEMCLKEN_AN9") (pintype "output"))
    )
    (net (code "161") (name "Net-(U2C-MEMODT0)") (class "Default")
      (node (ref "R285") (pin "1") (pinfunction "1_1") (pintype "passive"))
      (node (ref "U2") (pin "AH3") (pinfunction "MEMODT0_AH3") (pintype "output"))
    )
    (net (code "162") (name "Net-(U2C-RAS#)") (class "Default")
      (node (ref "R168") (pin "1") (pinfunction "1_1") (pintype "passive"))
      (node (ref "U2") (pin "AJ4") (pinfunction "RAS#_AJ4") (pintype "output"))
    )
    (net (code "163") (name "Net-(U2C-WE#)") (class "Default")
      (node (ref "R170") (pin "1") (pinfunction "1_1") (pintype "passive"))
      (node (ref "U2") (pin "AJ2") (pinfunction "WE#_AJ2") (pintype "output"))
    )
    (net (code "164") (name "Net-(U40-AVDD)") (class "Default")
      (node (ref "C205") (pin "2") (pinfunction "2_2") (pintype "passive"))
      (node (ref "C206") (pin "2") (pinfunction "2_2") (pintype "passive"))
      (node (ref "C207") (pin "2") (pinfunction "2_2") (pintype "passive"))
      (node (ref "L20") (pin "2") (pinfunction "2_2") (pintype "passive"))
      (node (ref "U40") (pin "8") (pinfunction "AVDD_8") (pintype "input"))
    )
    (net (code "165") (name "Net-(U40-FBIN#)") (class "Default")
      (node (ref "U40") (pin "25") (pinfunction "FBOUT#_25") (pintype "output"))
      (node (ref "U40") (pin "26") (pinfunction "FBIN#_26") (pintype "input"))
    )
    (net (code "166") (name "Net-(U40-FBIN)") (class "Default")
      (node (ref "U40") (pin "24") (pinfunction "FBOUT_24") (pintype "output"))
      (node (ref "U40") (pin "27") (pinfunction "FBIN_27") (pintype "input"))
    )
    (net (code "167") (name "Net-(U40-OE)") (class "Default")
      (node (ref "R171") (pin "1") (pinfunction "1_1") (pintype "passive"))
      (node (ref "U40") (pin "22") (pinfunction "OE_22") (pintype "input"))
    )
    (net (code "168") (name "Net-(U41-S3)") (class "Default")
      (node (ref "R189") (pin "1") (pinfunction "1_1") (pintype "passive"))
      (node (ref "U41") (pin "7") (pinfunction "S3_7") (pintype "input"))
    )
    (net (code "169") (name "Net-(U41-S5)") (class "Default")
      (node (ref "R191") (pin "1") (pinfunction "1_1") (pintype "passive"))
      (node (ref "U41") (pin "9") (pinfunction "S5_9") (pintype "input"))
    )
    (net (code "170") (name "Net-(U41-VTTSNS)") (class "Default")
      (node (ref "C218") (pin "2") (pinfunction "2_2") (pintype "passive"))
      (node (ref "R190") (pin "2") (pinfunction "2_2") (pintype "passive"))
      (node (ref "U41") (pin "5") (pinfunction "VTTSNS_5") (pintype "input"))
    )
    (net (code "171") (name "unconnected-(RP1-Pad1)") (class "Default")
      (node (ref "RP1") (pin "1") (pinfunction "1_1") (pintype "passive+no_connect"))
    )
    (net (code "172") (name "unconnected-(U2C-BANKSEL#1-PadAH1)") (class "Default")
      (node (ref "U2") (pin "AH1") (pinfunction "BANKSEL#1_AH1") (pintype "output+no_connect"))
    )
    (net (code "173") (name "unconnected-(U2C-MEMODT1-PadAG1)") (class "Default")
      (node (ref "U2") (pin "AG1") (pinfunction "MEMODT1_AG1") (pintype "output+no_connect"))
    )
    (net (code "174") (name "unconnected-(U40-Y0#-Pad37)") (class "Default")
      (node (ref "U40") (pin "37") (pinfunction "Y0#_37") (pintype "output+no_connect"))
    )
    (net (code "175") (name "unconnected-(U40-Y0-Pad38)") (class "Default")
      (node (ref "U40") (pin "38") (pinfunction "Y0_38") (pintype "output+no_connect"))
    )
    (net (code "176") (name "unconnected-(U40-Y2#-Pad2)") (class "Default")
      (node (ref "U40") (pin "2") (pinfunction "Y2#_2") (pintype "output+no_connect"))
    )
    (net (code "177") (name "unconnected-(U40-Y2-Pad3)") (class "Default")
      (node (ref "U40") (pin "3") (pinfunction "Y2_3") (pintype "output+no_connect"))
    )
    (net (code "178") (name "unconnected-(U40-Y3#-Pad12)") (class "Default")
      (node (ref "U40") (pin "12") (pinfunction "Y3#_12") (pintype "output+no_connect"))
    )
    (net (code "179") (name "unconnected-(U40-Y3-Pad11)") (class "Default")
      (node (ref "U40") (pin "11") (pinfunction "Y3_11") (pintype "output+no_connect"))
    )
    (net (code "180") (name "unconnected-(U40-Y4#-Pad13)") (class "Default")
      (node (ref "U40") (pin "13") (pinfunction "Y4#_13") (pintype "output+no_connect"))
    )
    (net (code "181") (name "unconnected-(U40-Y4-Pad14)") (class "Default")
      (node (ref "U40") (pin "14") (pinfunction "Y4_14") (pintype "output+no_connect"))
    )
    (net (code "182") (name "unconnected-(U40-Y5#-Pad35)") (class "Default")
      (node (ref "U40") (pin "35") (pinfunction "Y5#_35") (pintype "output+no_connect"))
    )
    (net (code "183") (name "unconnected-(U40-Y5-Pad34)") (class "Default")
      (node (ref "U40") (pin "34") (pinfunction "Y5_34") (pintype "output+no_connect"))
    )
    (net (code "184") (name "unconnected-(U40-Y6#-Pad32)") (class "Default")
      (node (ref "U40") (pin "32") (pinfunction "Y6#_32") (pintype "output+no_connect"))
    )
    (net (code "185") (name "unconnected-(U40-Y6-Pad33)") (class "Default")
      (node (ref "U40") (pin "33") (pinfunction "Y6_33") (pintype "output+no_connect"))
    )
  )
)
